# Sheet1.net
KiCad netlist of a schematic drawn in Altium Designer
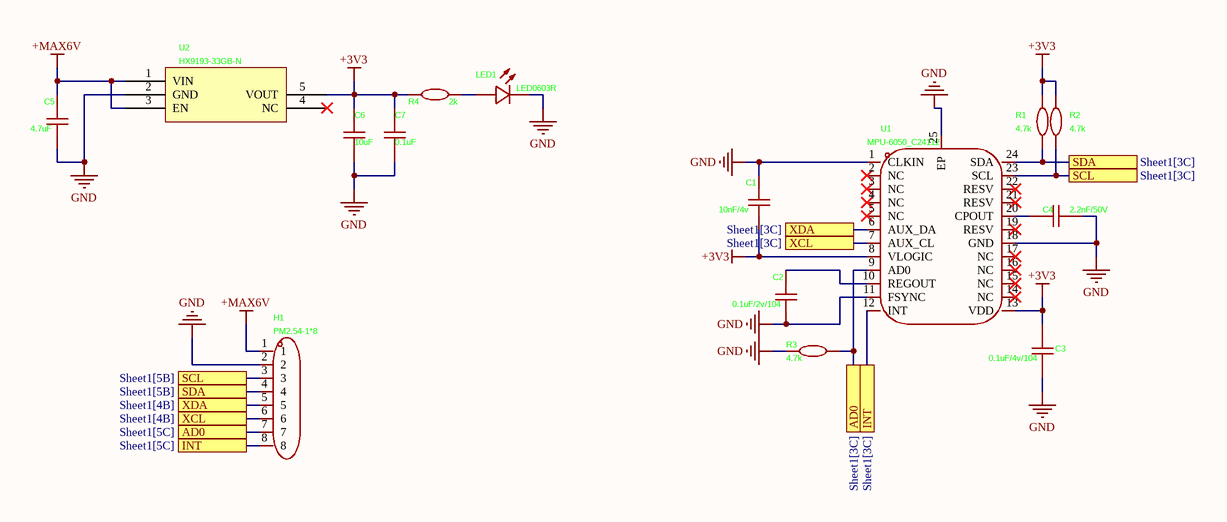
[diagram p0: Sheet1.SchDoc]

(export (version "E")
  (design (tool "Eeschema 10.0.6"))
  (components
    (comp (ref "C1")
      (value "10nF/4v")
      (footprint "C0402")
      (fields
        (field (name "MANUFACTURER") "muRata(村田)")
        (field (name "MANUFACTURER PART") "GRM1555C1H180JA01D")
        (field (name "TOLERANCE") "±5%")
      )
      (libsource (lib "altium-import") (part "root_1_GRM1555C1H180JA01D_"))
    )
    (comp (ref "C2")
      (value "0.1uF/2v/104")
      (footprint "C0402")
      (fields
        (field (name "MANUFACTURER") "muRata(村田)")
        (field (name "MANUFACTURER PART") "GRM1555C1H180JA01D")
        (field (name "TOLERANCE") "±5%")
      )
      (libsource (lib "altium-import") (part "root_1_GRM1555C1H180JA01D_"))
    )
    (comp (ref "C3")
      (value "0.1uF/4v/104")
      (footprint "C0402")
      (fields
        (field (name "MANUFACTURER") "muRata(村田)")
        (field (name "MANUFACTURER PART") "GRM1555C1H180JA01D")
        (field (name "TOLERANCE") "±5%")
      )
      (libsource (lib "altium-import") (part "root_1_GRM1555C1H180JA01D_"))
    )
    (comp (ref "C4")
      (value "2.2nF/50V")
      (footprint "C0402")
      (fields
        (field (name "MANUFACTURER") "muRata(村田)")
        (field (name "MANUFACTURER PART") "GRM1555C1H180JA01D")
        (field (name "TOLERANCE") "±5%")
      )
      (libsource (lib "altium-import") (part "root_0_GRM1555C1H180JA01D_"))
    )
    (comp (ref "C5")
      (value "4.7uF")
      (footprint "C0402")
      (fields
        (field (name "MANUFACTURER") "muRata(村田)")
        (field (name "MANUFACTURER PART") "GRM1555C1H180JA01D")
        (field (name "TOLERANCE") "±5%")
      )
      (libsource (lib "altium-import") (part "root_1_GRM1555C1H180JA01D_"))
    )
    (comp (ref "C6")
      (value "10uF")
      (footprint "C0402")
      (fields
        (field (name "MANUFACTURER") "muRata(村田)")
        (field (name "MANUFACTURER PART") "GRM1555C1H180JA01D")
        (field (name "TOLERANCE") "±5%")
      )
      (libsource (lib "altium-import") (part "root_1_GRM1555C1H180JA01D_"))
    )
    (comp (ref "C7")
      (value "0.1uF")
      (footprint "C0402")
      (fields
        (field (name "MANUFACTURER") "muRata(村田)")
        (field (name "MANUFACTURER PART") "GRM1555C1H180JA01D")
        (field (name "TOLERANCE") "±5%")
      )
      (libsource (lib "altium-import") (part "root_1_GRM1555C1H180JA01D_"))
    )
    (comp (ref "H1")
      (value "PM2.54-1*8")
      (footprint "HDR-TH_8P-P2.54-V-F")
      (fields (field (name "MANUFACTURER") "ZHOURI(洲日)"))
      (libsource (lib "altium-import") (part "root_0_PM2.54-1*8_"))
    )
    (comp (ref "LED1")
      (value "LED0603R")
      (footprint "LED0603-FD")
      (fields (field (name "MANUFACTURER") "YONGYUTAI(永裕泰)") (field (name "MANUFACTURER PART") "YLED0603R"))
      (libsource (lib "altium-import") (part "root_0_YLED0603R_"))
    )
    (comp (ref "R1")
      (value "4.7k")
      (footprint "R0603")
      (fields
        (field (name "MANUFACTURER") "YAGEO(国巨)")
        (field (name "MANUFACTURER PART") "RC0603FR-0710KL")
        (field (name "TOLERANCE") "±1%")
      )
      (libsource (lib "altium-import") (part "root_1_RC0603FR-0710KL_"))
    )
    (comp (ref "R2")
      (value "4.7k")
      (footprint "R0603")
      (fields
        (field (name "MANUFACTURER") "YAGEO(国巨)")
        (field (name "MANUFACTURER PART") "RC0603FR-0710KL")
        (field (name "TOLERANCE") "±1%")
      )
      (libsource (lib "altium-import") (part "root_1_RC0603FR-0710KL_"))
    )
    (comp (ref "R3")
      (value "4.7k")
      (footprint "R0603")
      (fields
        (field (name "MANUFACTURER") "YAGEO(国巨)")
        (field (name "MANUFACTURER PART") "RC0603FR-0710KL")
        (field (name "TOLERANCE") "±1%")
      )
      (libsource (lib "altium-import") (part "root_0_RC0603FR-0710KL_"))
    )
    (comp (ref "R4")
      (value "2k")
      (footprint "R0603")
      (fields
        (field (name "MANUFACTURER") "YAGEO(国巨)")
        (field (name "MANUFACTURER PART") "RC0603FR-0710KL")
        (field (name "TOLERANCE") "±1%")
      )
      (libsource (lib "altium-import") (part "root_0_RC0603FR-0710KL_"))
    )
    (comp (ref "U1")
      (value "MPU-6050_C24112")
      (footprint "QFN-24_L4.0-W4.0-P0.50-BL-EP2.7")
      (fields
        (field (name "MANUFACTURER") "TDK InvenSense(应美盛)")
        (field (name "MANUFACTURER PART") "MPU-6050")
      )
      (libsource (lib "altium-import") (part "root_0_MPU-6050_"))
    )
    (comp (ref "U2")
      (value "HX9193-33GB-N")
      (footprint "SOT-23-5_L2.9-W1.6-P0.95-LS2.8-BL")
      (fields (field (name "MANUFACTURER") "HX(恒佳兴)"))
      (libsource (lib "altium-import") (part "root_0_HX9193-33GB-N_"))
    )
  )
  (nets
    (net (code "1") (name "+3V3") (class "Default")
      (node (ref "C1") (pin "1") (pinfunction "1_1") (pintype "passive"))
      (node (ref "C3") (pin "2") (pinfunction "2_2") (pintype "passive"))
      (node (ref "C6") (pin "2") (pinfunction "2_2") (pintype "passive"))
      (node (ref "C7") (pin "2") (pinfunction "2_2") (pintype "passive"))
      (node (ref "R1") (pin "2") (pinfunction "2_2") (pintype "passive"))
      (node (ref "R2") (pin "2") (pinfunction "2_2") (pintype "passive"))
      (node (ref "R4") (pin "1") (pinfunction "1_1") (pintype "passive"))
      (node (ref "U1") (pin "13") (pinfunction "VDD_13") (pintype "passive"))
      (node (ref "U1") (pin "8") (pinfunction "VLOGIC_8") (pintype "passive"))
      (node (ref "U2") (pin "5") (pinfunction "VOUT_5") (pintype "passive"))
    )
    (net (code "2") (name "+MAX6V") (class "Default")
      (node (ref "C5") (pin "2") (pinfunction "2_2") (pintype "passive"))
      (node (ref "H1") (pin "1") (pinfunction "1_1") (pintype "passive"))
      (node (ref "U2") (pin "1") (pinfunction "VIN_1") (pintype "passive"))
      (node (ref "U2") (pin "3") (pinfunction "EN_3") (pintype "passive"))
    )
    (net (code "3") (name "/AD0") (class "Default")
      (node (ref "H1") (pin "7") (pinfunction "7_7") (pintype "passive"))
      (node (ref "R3") (pin "2") (pinfunction "2_2") (pintype "passive"))
      (node (ref "U1") (pin "9") (pinfunction "AD0_9") (pintype "passive"))
    )
    (net (code "4") (name "/INT") (class "Default")
      (node (ref "H1") (pin "8") (pinfunction "8_8") (pintype "passive"))
      (node (ref "U1") (pin "12") (pinfunction "INT_12") (pintype "passive"))
    )
    (net (code "5") (name "/SCL") (class "Default")
      (node (ref "H1") (pin "3") (pinfunction "3_3") (pintype "passive"))
      (node (ref "R2") (pin "1") (pinfunction "1_1") (pintype "passive"))
      (node (ref "U1") (pin "23") (pinfunction "SCL_23") (pintype "passive"))
    )
    (net (code "6") (name "/SDA") (class "Default")
      (node (ref "H1") (pin "4") (pinfunction "4_4") (pintype "passive"))
      (node (ref "R1") (pin "1") (pinfunction "1_1") (pintype "passive"))
      (node (ref "U1") (pin "24") (pinfunction "SDA_24") (pintype "passive"))
    )
    (net (code "7") (name "/XCL") (class "Default")
      (node (ref "H1") (pin "6") (pinfunction "6_6") (pintype "passive"))
      (node (ref "U1") (pin "7") (pinfunction "AUX_CL_7") (pintype "passive"))
    )
    (net (code "8") (name "/XDA") (class "Default")
      (node (ref "H1") (pin "5") (pinfunction "5_5") (pintype "passive"))
      (node (ref "U1") (pin "6") (pinfunction "AUX_DA_6") (pintype "passive"))
    )
    (net (code "9") (name "GND") (class "Default")
      (node (ref "C1") (pin "2") (pinfunction "2_2") (pintype "passive"))
      (node (ref "C2") (pin "1") (pinfunction "1_1") (pintype "passive"))
      (node (ref "C3") (pin "1") (pinfunction "1_1") (pintype "passive"))
      (node (ref "C4") (pin "2") (pinfunction "2_2") (pintype "passive"))
      (node (ref "C5") (pin "1") (pinfunction "1_1") (pintype "passive"))
      (node (ref "C6") (pin "1") (pinfunction "1_1") (pintype "passive"))
      (node (ref "C7") (pin "1") (pinfunction "1_1") (pintype "passive"))
      (node (ref "H1") (pin "2") (pinfunction "2_2") (pintype "passive"))
      (node (ref "LED1") (pin "2") (pinfunction "-_2") (pintype "passive"))
      (node (ref "R3") (pin "1") (pinfunction "1_1") (pintype "passive"))
      (node (ref "U1") (pin "1") (pinfunction "CLKIN_1") (pintype "passive"))
      (node (ref "U1") (pin "11") (pinfunction "FSYNC_11") (pintype "passive"))
      (node (ref "U1") (pin "18") (pinfunction "GND_18") (pintype "passive"))
      (node (ref "U1") (pin "25") (pinfunction "EP_25") (pintype "passive"))
      (node (ref "U2") (pin "2") (pinfunction "GND_2") (pintype "passive"))
    )
    (net (code "10") (name "Net-(LED1-+)") (class "Default")
      (node (ref "LED1") (pin "1") (pinfunction "+_1") (pintype "passive"))
      (node (ref "R4") (pin "2") (pinfunction "2_2") (pintype "passive"))
    )
    (net (code "11") (name "Net-(U1-CPOUT)") (class "Default")
      (node (ref "C4") (pin "1") (pinfunction "1_1") (pintype "passive"))
      (node (ref "U1") (pin "20") (pinfunction "CPOUT_20") (pintype "passive"))
    )
    (net (code "12") (name "Net-(U1-REGOUT)") (class "Default")
      (node (ref "C2") (pin "2") (pinfunction "2_2") (pintype "passive"))
      (node (ref "U1") (pin "10") (pinfunction "REGOUT_10") (pintype "passive"))
    )
    (net (code "13") (name "unconnected-(U1-NC-Pad2)") (class "Default")
      (node (ref "U1") (pin "2") (pinfunction "NC_2") (pintype "passive+no_connect"))
    )
    (net (code "14") (name "unconnected-(U1-NC-Pad3)") (class "Default")
      (node (ref "U1") (pin "3") (pinfunction "NC_3") (pintype "passive+no_connect"))
    )
    (net (code "15") (name "unconnected-(U1-NC-Pad4)") (class "Default")
      (node (ref "U1") (pin "4") (pinfunction "NC_4") (pintype "passive+no_connect"))
    )
    (net (code "16") (name "unconnected-(U1-NC-Pad5)") (class "Default")
      (node (ref "U1") (pin "5") (pinfunction "NC_5") (pintype "passive+no_connect"))
    )
    (net (code "17") (name "unconnected-(U1-NC-Pad14)") (class "Default")
      (node (ref "U1") (pin "14") (pinfunction "NC_14") (pintype "passive+no_connect"))
    )
    (net (code "18") (name "unconnected-(U1-NC-Pad15)") (class "Default")
      (node (ref "U1") (pin "15") (pinfunction "NC_15") (pintype "passive+no_connect"))
    )
    (net (code "19") (name "unconnected-(U1-NC-Pad16)") (class "Default")
      (node (ref "U1") (pin "16") (pinfunction "NC_16") (pintype "passive+no_connect"))
    )
    (net (code "20") (name "unconnected-(U1-NC-Pad17)") (class "Default")
      (node (ref "U1") (pin "17") (pinfunction "NC_17") (pintype "passive+no_connect"))
    )
    (net (code "21") (name "unconnected-(U1-RESV-Pad19)") (class "Default")
      (node (ref "U1") (pin "19") (pinfunction "RESV_19") (pintype "passive+no_connect"))
    )
    (net (code "22") (name "unconnected-(U1-RESV-Pad21)") (class "Default")
      (node (ref "U1") (pin "21") (pinfunction "RESV_21") (pintype "passive+no_connect"))
    )
    (net (code "23") (name "unconnected-(U1-RESV-Pad22)") (class "Default")
      (node (ref "U1") (pin "22") (pinfunction "RESV_22") (pintype "passive+no_connect"))
    )
    (net (code "24") (name "unconnected-(U2-NC-Pad4)") (class "Default")
      (node (ref "U2") (pin "4") (pinfunction "NC_4") (pintype "passive+no_connect"))
    )
  )
)
